# smokedetector.net
KiCad netlist of a schematic drawn in EAGLE
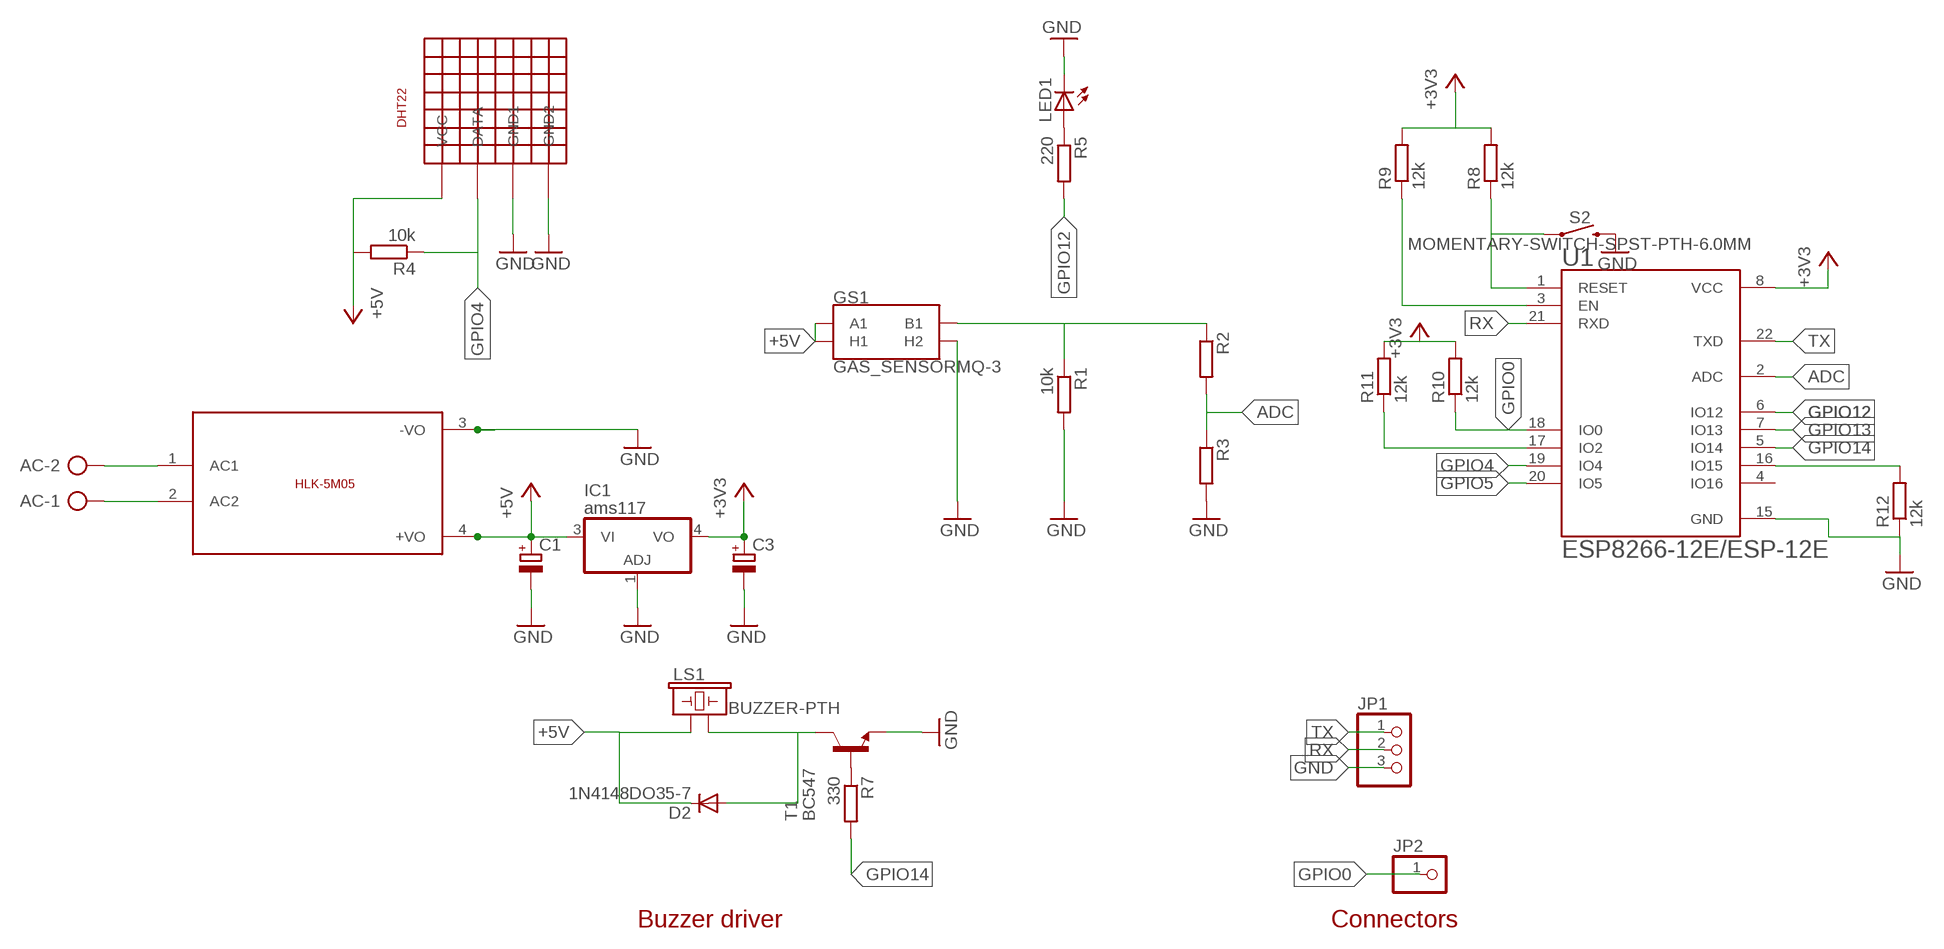
[diagram p0: schematic, sheet 1]

(export (version "E")
  (design (tool "Eeschema 10.0.6"))
  (components
    (comp (ref "AC")
      (value "AK500/2-H")
      (footprint "eagle-import:AK500_2-H")
      (libsource (lib "eagle-import") (part "AK500/2-H"))
    )
    (comp (ref "C1")
      (value "CPOL-EUE2.5-6")
      (footprint "eagle-import:E2,5-6")
      (libsource (lib "eagle-import") (part "CPOL-EUE2.5-6"))
    )
    (comp (ref "C3")
      (value "CPOL-EUE2.5-6")
      (footprint "eagle-import:E2,5-6")
      (libsource (lib "eagle-import") (part "CPOL-EUE2.5-6"))
    )
    (comp (ref "D2")
      (value "1N4148DO35-7")
      (footprint "eagle-import:DO35-7")
      (libsource (lib "eagle-import") (part "1N4148DO35-7"))
    )
    (comp (ref "DHT22")
      (value "DHT22")
      (footprint "eagle-import:DHT22")
      (libsource (lib "eagle-import") (part "DHT22"))
    )
    (comp (ref "GS1")
      (value "GAS_SENSORMQ-3")
      (footprint "eagle-import:GAS_SENSOR")
      (libsource (lib "eagle-import") (part "GAS_SENSORMQ-3"))
    )
    (comp (ref "IC1")
      (value "ams117")
      (footprint "eagle-import:SOT223")
      (libsource (lib "eagle-import") (part "317EMP"))
    )
    (comp (ref "JP1")
      (value "PINHD-1X3CB")
      (footprint "eagle-import:1X03-CLEANBIG")
      (libsource (lib "eagle-import") (part "PINHD-1X3CB"))
    )
    (comp (ref "JP2")
      (value "PINHD-1X1CB")
      (footprint "eagle-import:1X01-CLEANBIG")
      (libsource (lib "eagle-import") (part "PINHD-1X1CB"))
    )
    (comp (ref "LED1")
      (value "LED5MM")
      (footprint "eagle-import:LED5MM")
      (libsource (lib "eagle-import") (part "LED5MM"))
    )
    (comp (ref "LS1")
      (value "BUZZER-PTH")
      (footprint "eagle-import:BUZZER-12MM")
      (libsource (lib "eagle-import") (part "BUZZER-PTH"))
    )
    (comp (ref "R1")
      (value "10k")
      (footprint "eagle-import:0204V")
      (libsource (lib "eagle-import") (part "R-EU_0204/2V"))
    )
    (comp (ref "R2")
      (value "R-EU_0204/2V")
      (footprint "eagle-import:0204V")
      (libsource (lib "eagle-import") (part "R-EU_0204/2V"))
    )
    (comp (ref "R3")
      (value "R-EU_0204/2V")
      (footprint "eagle-import:0204V")
      (libsource (lib "eagle-import") (part "R-EU_0204/2V"))
    )
    (comp (ref "R4")
      (value "10k")
      (footprint "eagle-import:0204V")
      (libsource (lib "eagle-import") (part "R-EU_0204/2V"))
    )
    (comp (ref "R5")
      (value "220")
      (footprint "eagle-import:0204V")
      (libsource (lib "eagle-import") (part "R-EU_0204/2V"))
    )
    (comp (ref "R7")
      (value "330")
      (footprint "eagle-import:0204V")
      (libsource (lib "eagle-import") (part "R-EU_0204/2V"))
    )
    (comp (ref "R8")
      (value "12k")
      (footprint "eagle-import:0204V")
      (libsource (lib "eagle-import") (part "R-EU_0204/2V"))
    )
    (comp (ref "R9")
      (value "12k")
      (footprint "eagle-import:0204V")
      (libsource (lib "eagle-import") (part "R-EU_0204/2V"))
    )
    (comp (ref "R10")
      (value "12k")
      (footprint "eagle-import:0204V")
      (libsource (lib "eagle-import") (part "R-EU_0204/2V"))
    )
    (comp (ref "R11")
      (value "12k")
      (footprint "eagle-import:0204V")
      (libsource (lib "eagle-import") (part "R-EU_0204/2V"))
    )
    (comp (ref "R12")
      (value "12k")
      (footprint "eagle-import:0204V")
      (libsource (lib "eagle-import") (part "R-EU_0204/2V"))
    )
    (comp (ref "S2")
      (value "MOMENTARY-SWITCH-SPST-PTH-6.0MM")
      (footprint "eagle-import:TACTILE_SWITCH_PTH_6.0MM_KIT")
      (libsource (lib "eagle-import") (part "MOMENTARY-SWITCH-SPST-PTH-6.0MM-KIT"))
    )
    (comp (ref "T1")
      (value "BC547")
      (footprint "eagle-import:TO92")
      (libsource (lib "eagle-import") (part "BC547"))
    )
    (comp (ref "U$2")
      (value "HLK-5M05")
      (footprint "eagle-import:HLK-5M05")
      (fields (field (name "MF") "Hi-link"))
      (libsource (lib "eagle-import") (part "HLK-5M05"))
    )
    (comp (ref "U1")
      (value "ESP8266-12E/ESP-12E")
      (footprint "eagle-import:XCVR_ESP8266-12E_ESP-12E")
      (fields (field (name "MF") "AI-Thinker"))
      (libsource (lib "eagle-import") (part "ESP8266-12E/ESP-12E"))
    )
  )
  (nets
    (net (code "1") (name "+3V3") (class "Default")
      (node (ref "C3") (pin "+") (pinfunction "+_+") (pintype "passive"))
      (node (ref "IC1") (pin "4") (pinfunction "VO_4") (pintype "passive"))
      (node (ref "R10") (pin "2") (pinfunction "2_2") (pintype "passive"))
      (node (ref "R11") (pin "2") (pinfunction "2_2") (pintype "passive"))
      (node (ref "R8") (pin "2") (pinfunction "2_2") (pintype "passive"))
      (node (ref "R9") (pin "2") (pinfunction "2_2") (pintype "passive"))
      (node (ref "U1") (pin "8") (pinfunction "VCC_8") (pintype "power_in"))
    )
    (net (code "2") (name "+5V") (class "Default")
      (node (ref "C1") (pin "+") (pinfunction "+_+") (pintype "passive"))
      (node (ref "D2") (pin "C") (pinfunction "C_C") (pintype "passive"))
      (node (ref "DHT22") (pin "P$1") (pinfunction "VCC_P$1") (pintype "bidirectional"))
      (node (ref "GS1") (pin "A1") (pinfunction "A1_A1") (pintype "bidirectional"))
      (node (ref "GS1") (pin "HA") (pinfunction "H1_HA") (pintype "bidirectional"))
      (node (ref "IC1") (pin "3") (pinfunction "VI_3") (pintype "input"))
      (node (ref "LS1") (pin "+") (pinfunction "1_+") (pintype "passive"))
      (node (ref "R4") (pin "2") (pinfunction "2_2") (pintype "passive"))
      (node (ref "U$2") (pin "4") (pinfunction "+VO_4") (pintype "bidirectional"))
    )
    (net (code "3") (name "ADC") (class "Default")
      (node (ref "R2") (pin "2") (pinfunction "2_2") (pintype "passive"))
      (node (ref "R3") (pin "1") (pinfunction "1_1") (pintype "passive"))
      (node (ref "U1") (pin "2") (pinfunction "ADC_2") (pintype "passive"))
    )
    (net (code "4") (name "GND") (class "Default")
      (node (ref "C1") (pin "-") (pinfunction "-_-") (pintype "passive"))
      (node (ref "C3") (pin "-") (pinfunction "-_-") (pintype "passive"))
      (node (ref "DHT22") (pin "P$3") (pinfunction "GND1_P$3") (pintype "bidirectional"))
      (node (ref "DHT22") (pin "P$4") (pinfunction "GND2_P$4") (pintype "bidirectional"))
      (node (ref "GS1") (pin "HB") (pinfunction "H2_HB") (pintype "bidirectional"))
      (node (ref "IC1") (pin "1") (pinfunction "ADJ_1") (pintype "input"))
      (node (ref "JP1") (pin "3") (pinfunction "3_3") (pintype "passive"))
      (node (ref "LED1") (pin "K") (pinfunction "C_K") (pintype "passive"))
      (node (ref "R1") (pin "2") (pinfunction "2_2") (pintype "passive"))
      (node (ref "R12") (pin "1") (pinfunction "1_1") (pintype "passive"))
      (node (ref "R3") (pin "2") (pinfunction "2_2") (pintype "passive"))
      (node (ref "S2") (pin "3") (pinfunction "2_3") (pintype "passive"))
      (node (ref "T1") (pin "1") (pinfunction "E_1") (pintype "passive"))
      (node (ref "U$2") (pin "3") (pinfunction "-VO_3") (pintype "bidirectional"))
      (node (ref "U1") (pin "15") (pinfunction "GND_15") (pintype "power_in"))
    )
    (net (code "5") (name "GPIO0") (class "Default")
      (node (ref "JP2") (pin "1") (pinfunction "1_1") (pintype "passive"))
      (node (ref "R10") (pin "1") (pinfunction "1_1") (pintype "passive"))
      (node (ref "U1") (pin "18") (pinfunction "IO0_18") (pintype "bidirectional"))
    )
    (net (code "6") (name "GPIO4") (class "Default")
      (node (ref "DHT22") (pin "P$2") (pinfunction "DATA_P$2") (pintype "bidirectional"))
      (node (ref "R4") (pin "1") (pinfunction "1_1") (pintype "passive"))
      (node (ref "U1") (pin "19") (pinfunction "IO4_19") (pintype "bidirectional"))
    )
    (net (code "7") (name "GPIO5") (class "Default")
      (node (ref "U1") (pin "20") (pinfunction "IO5_20") (pintype "bidirectional"))
    )
    (net (code "8") (name "GPIO12") (class "Default")
      (node (ref "R5") (pin "2") (pinfunction "2_2") (pintype "passive"))
      (node (ref "U1") (pin "6") (pinfunction "IO12_6") (pintype "bidirectional"))
    )
    (net (code "9") (name "GPIO13") (class "Default")
      (node (ref "U1") (pin "7") (pinfunction "IO13_7") (pintype "bidirectional"))
    )
    (net (code "10") (name "GPIO14") (class "Default")
      (node (ref "R7") (pin "2") (pinfunction "2_2") (pintype "passive"))
      (node (ref "U1") (pin "5") (pinfunction "IO14_5") (pintype "bidirectional"))
    )
    (net (code "11") (name "Net-(ACA-KL)") (class "Default")
      (node (ref "AC") (pin "1") (pinfunction "KL_1") (pintype "passive"))
      (node (ref "U$2") (pin "2") (pinfunction "AC2_2") (pintype "bidirectional"))
    )
    (net (code "12") (name "Net-(ACB-KL)") (class "Default")
      (node (ref "AC") (pin "2") (pinfunction "KL_2") (pintype "passive"))
      (node (ref "U$2") (pin "1") (pinfunction "AC1_1") (pintype "bidirectional"))
    )
    (net (code "13") (name "Net-(GS1-PadB1)") (class "Default")
      (node (ref "GS1") (pin "B1") (pinfunction "B1_B1") (pintype "bidirectional"))
      (node (ref "R1") (pin "1") (pinfunction "1_1") (pintype "passive"))
      (node (ref "R2") (pin "1") (pinfunction "1_1") (pintype "passive"))
    )
    (net (code "14") (name "Net-(LED1-PadA)") (class "Default")
      (node (ref "LED1") (pin "A") (pinfunction "A_A") (pintype "passive"))
      (node (ref "R5") (pin "1") (pinfunction "1_1") (pintype "passive"))
    )
    (net (code "15") (name "Net-(LS1-2)") (class "Default")
      (node (ref "D2") (pin "A") (pinfunction "A_A") (pintype "passive"))
      (node (ref "LS1") (pin "-") (pinfunction "2_-") (pintype "passive"))
      (node (ref "T1") (pin "3") (pinfunction "C_3") (pintype "passive"))
    )
    (net (code "16") (name "Net-(T1-B)") (class "Default")
      (node (ref "R7") (pin "1") (pinfunction "1_1") (pintype "passive"))
      (node (ref "T1") (pin "2") (pinfunction "B_2") (pintype "passive"))
    )
    (net (code "17") (name "Net-(U1-EN)") (class "Default")
      (node (ref "R9") (pin "1") (pinfunction "1_1") (pintype "passive"))
      (node (ref "U1") (pin "3") (pinfunction "EN_3") (pintype "input"))
    )
    (net (code "18") (name "Net-(U1-IO2)") (class "Default")
      (node (ref "R11") (pin "1") (pinfunction "1_1") (pintype "passive"))
      (node (ref "U1") (pin "17") (pinfunction "IO2_17") (pintype "bidirectional"))
    )
    (net (code "19") (name "Net-(U1-IO15)") (class "Default")
      (node (ref "R12") (pin "2") (pinfunction "2_2") (pintype "passive"))
      (node (ref "U1") (pin "16") (pinfunction "IO15_16") (pintype "bidirectional"))
    )
    (net (code "20") (name "Net-(U1-RESET)") (class "Default")
      (node (ref "R8") (pin "1") (pinfunction "1_1") (pintype "passive"))
      (node (ref "S2") (pin "1") (pinfunction "1_1") (pintype "passive"))
      (node (ref "U1") (pin "1") (pinfunction "RESET_1") (pintype "input"))
    )
    (net (code "21") (name "RX") (class "Default")
      (node (ref "JP1") (pin "2") (pinfunction "2_2") (pintype "passive"))
      (node (ref "U1") (pin "21") (pinfunction "RXD_21") (pintype "input"))
    )
    (net (code "22") (name "TX") (class "Default")
      (node (ref "JP1") (pin "1") (pinfunction "1_1") (pintype "passive"))
      (node (ref "U1") (pin "22") (pinfunction "TXD_22") (pintype "output"))
    )
    (net (code "23") (name "unconnected-(U1-IO16-Pad4)") (class "Default")
      (node (ref "U1") (pin "4") (pinfunction "IO16_4") (pintype "bidirectional"))
    )
  )
)
